# LED_Matrix.net
KiCad netlist of a schematic drawn in Altium Designer
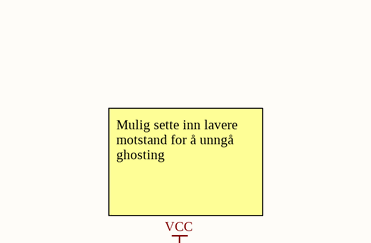
[diagram p0: LED Matrix.SchDoc, top left]
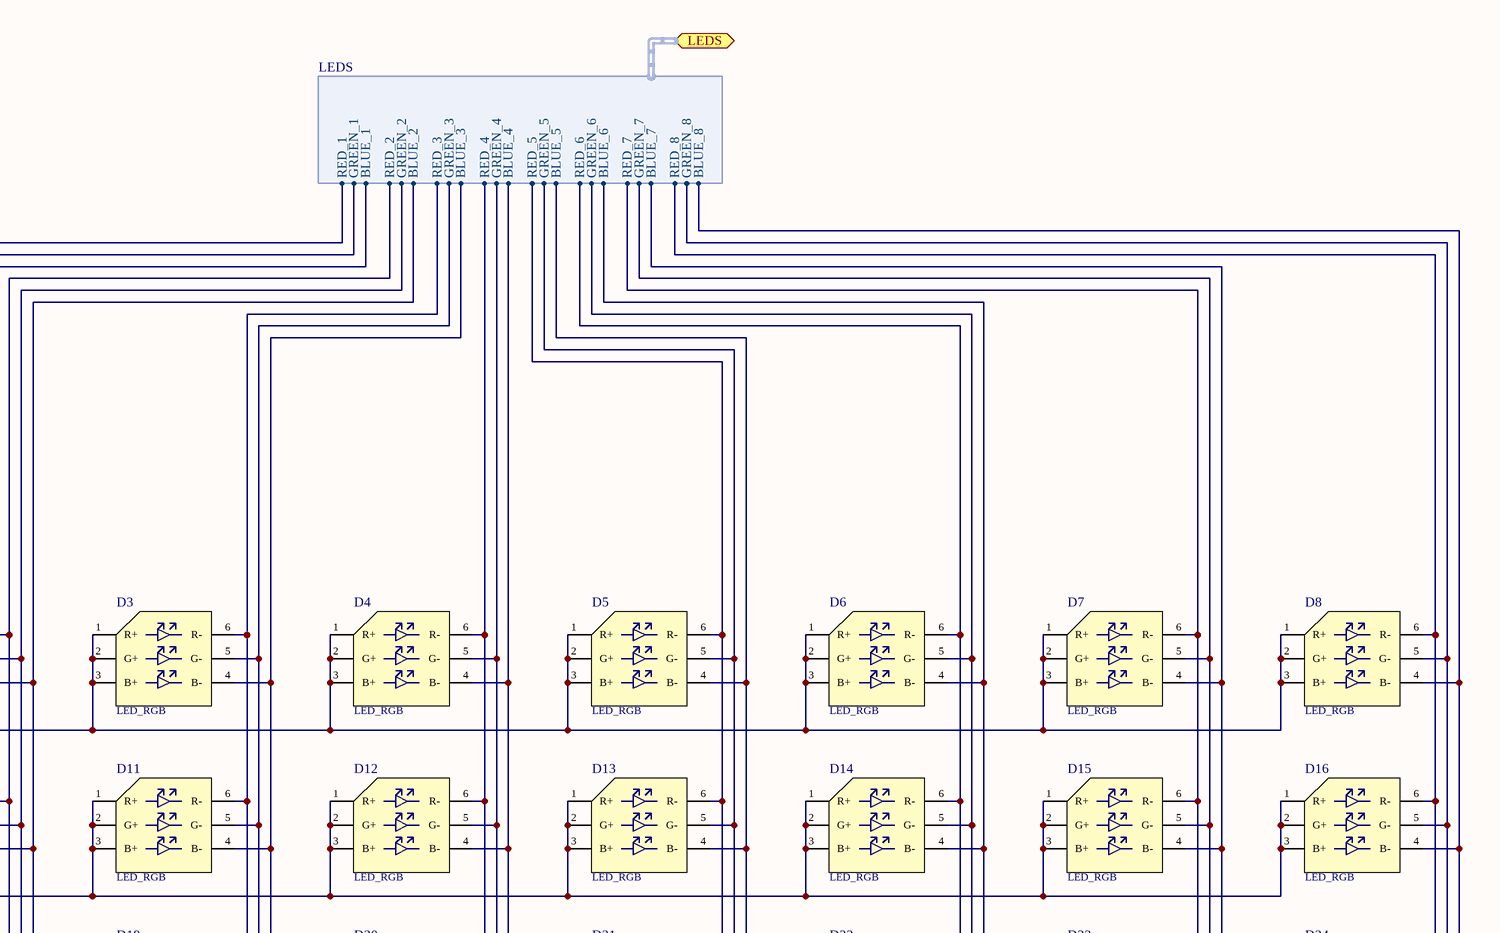
[diagram p1: LED Matrix.SchDoc, top right]
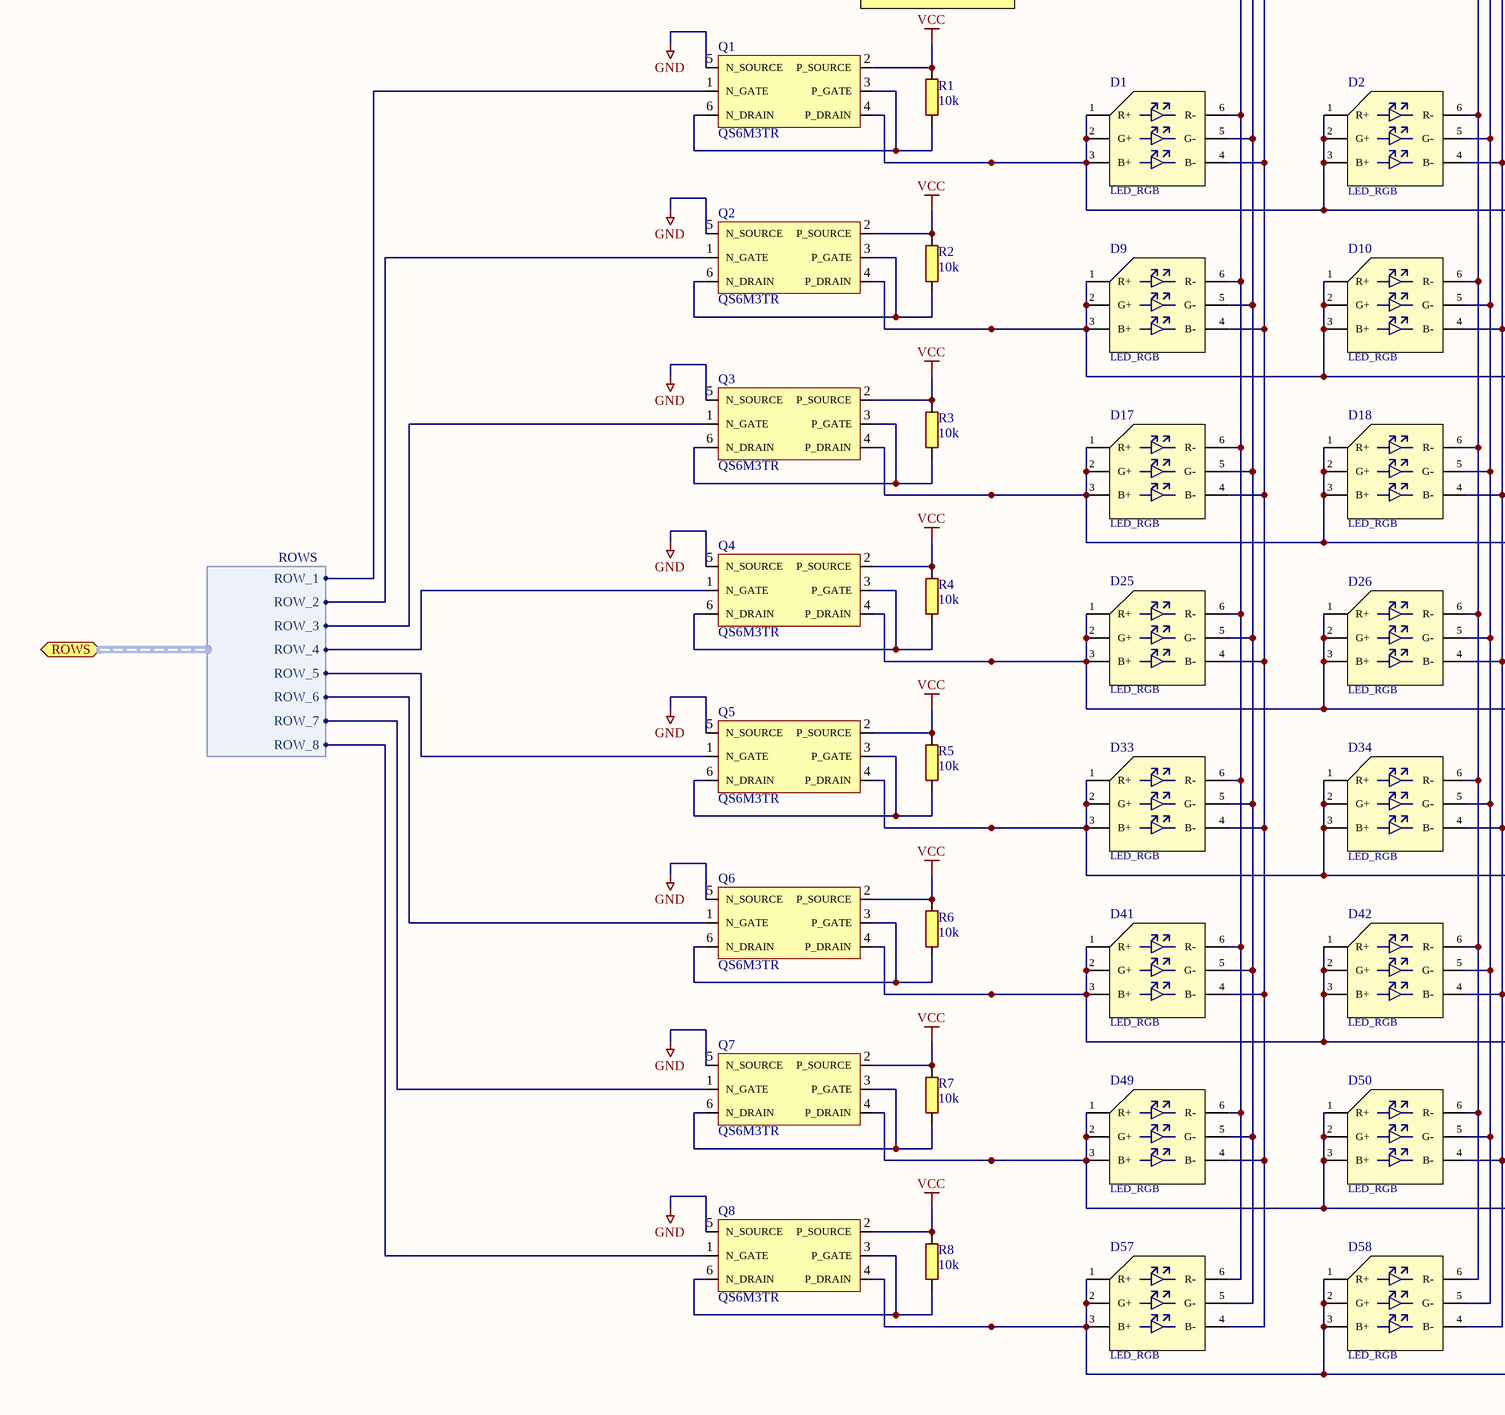
[diagram p2: LED Matrix.SchDoc, bottom left]
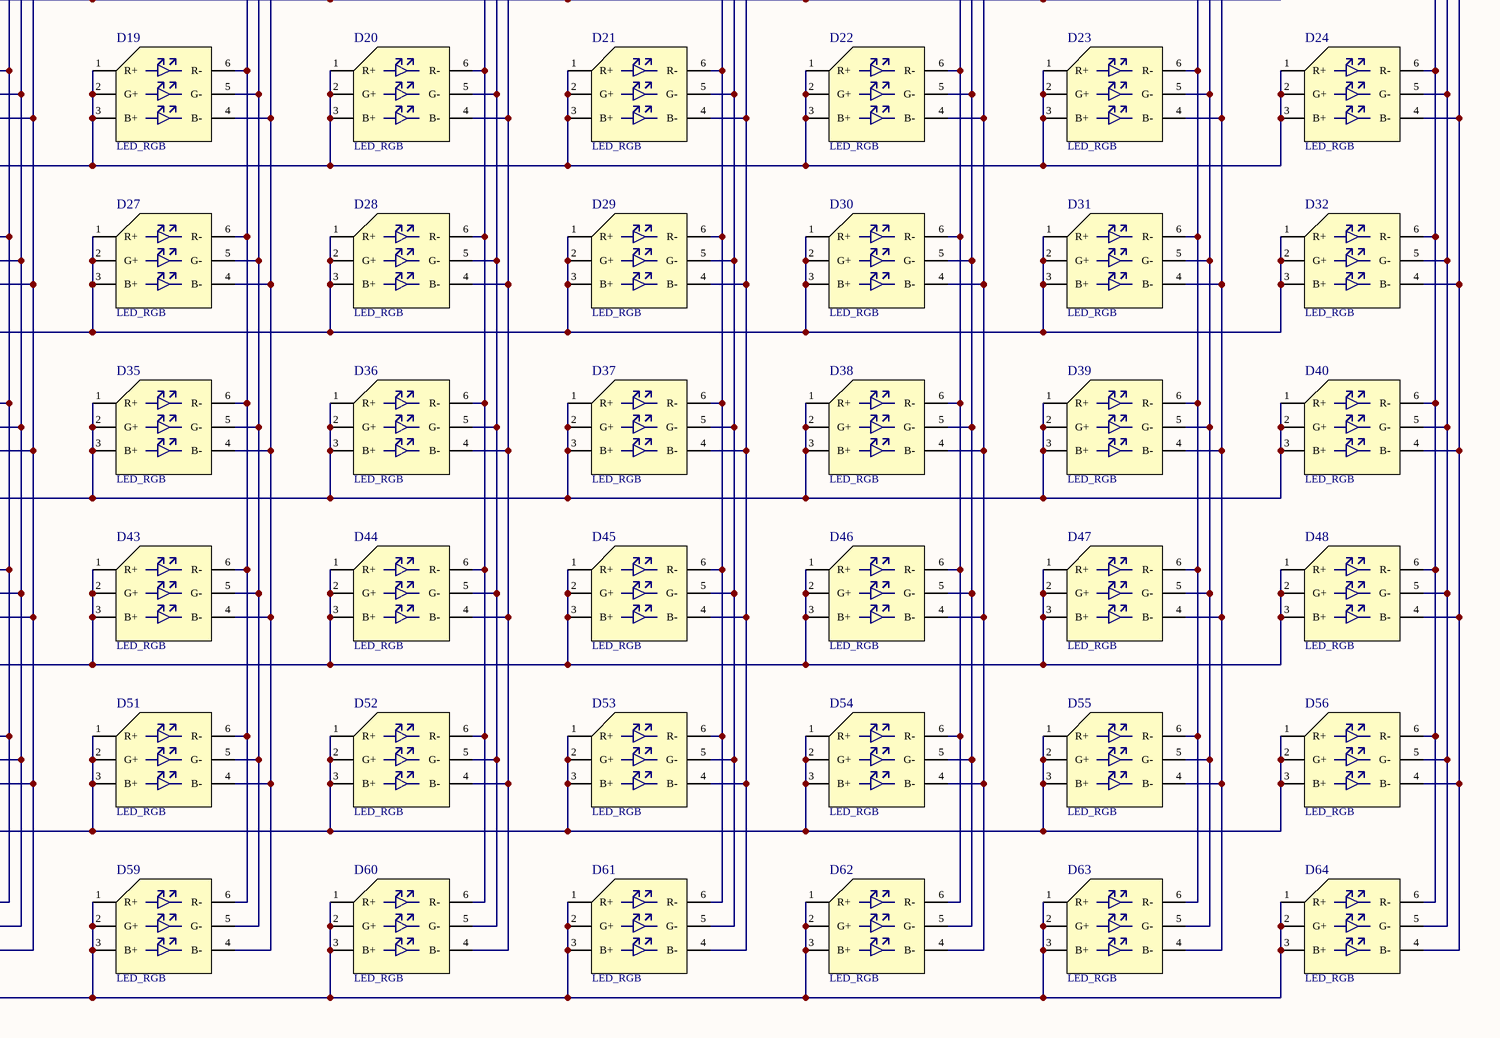
[diagram p3: LED Matrix.SchDoc, bottom right]

(export (version "E")
  (design (tool "Eeschema 10.0.6"))
  (components
    (comp (ref "D1")
      (value "LED_RGB")
      (footprint "LED5050_RGB_N")
      (description "LED RGB, independent colors")
      (libsource (lib "OVLib") (part "LED_RGB_IND_CHIP"))
    )
    (comp (ref "D2")
      (value "LED_RGB")
      (footprint "LED5050_RGB_N")
      (description "LED RGB, independent colors")
      (libsource (lib "OVLib") (part "LED_RGB_IND_CHIP"))
    )
    (comp (ref "D3")
      (value "LED_RGB")
      (footprint "LED5050_RGB_N")
      (description "LED RGB, independent colors")
      (libsource (lib "OVLib") (part "LED_RGB_IND_CHIP"))
    )
    (comp (ref "D4")
      (value "LED_RGB")
      (footprint "LED5050_RGB_N")
      (description "LED RGB, independent colors")
      (libsource (lib "OVLib") (part "LED_RGB_IND_CHIP"))
    )
    (comp (ref "D5")
      (value "LED_RGB")
      (footprint "LED5050_RGB_N")
      (description "LED RGB, independent colors")
      (libsource (lib "OVLib") (part "LED_RGB_IND_CHIP"))
    )
    (comp (ref "D6")
      (value "LED_RGB")
      (footprint "LED5050_RGB_N")
      (description "LED RGB, independent colors")
      (libsource (lib "OVLib") (part "LED_RGB_IND_CHIP"))
    )
    (comp (ref "D7")
      (value "LED_RGB")
      (footprint "LED5050_RGB_N")
      (description "LED RGB, independent colors")
      (libsource (lib "OVLib") (part "LED_RGB_IND_CHIP"))
    )
    (comp (ref "D8")
      (value "LED_RGB")
      (footprint "LED5050_RGB_N")
      (description "LED RGB, independent colors")
      (libsource (lib "OVLib") (part "LED_RGB_IND_CHIP"))
    )
    (comp (ref "D9")
      (value "LED_RGB")
      (footprint "LED5050_RGB_N")
      (description "LED RGB, independent colors")
      (libsource (lib "OVLib") (part "LED_RGB_IND_CHIP"))
    )
    (comp (ref "D10")
      (value "LED_RGB")
      (footprint "LED5050_RGB_N")
      (description "LED RGB, independent colors")
      (libsource (lib "OVLib") (part "LED_RGB_IND_CHIP"))
    )
    (comp (ref "D11")
      (value "LED_RGB")
      (footprint "LED5050_RGB_N")
      (description "LED RGB, independent colors")
      (libsource (lib "OVLib") (part "LED_RGB_IND_CHIP"))
    )
    (comp (ref "D12")
      (value "LED_RGB")
      (footprint "LED5050_RGB_N")
      (description "LED RGB, independent colors")
      (libsource (lib "OVLib") (part "LED_RGB_IND_CHIP"))
    )
    (comp (ref "D13")
      (value "LED_RGB")
      (footprint "LED5050_RGB_N")
      (description "LED RGB, independent colors")
      (libsource (lib "OVLib") (part "LED_RGB_IND_CHIP"))
    )
    (comp (ref "D14")
      (value "LED_RGB")
      (footprint "LED5050_RGB_N")
      (description "LED RGB, independent colors")
      (libsource (lib "OVLib") (part "LED_RGB_IND_CHIP"))
    )
    (comp (ref "D15")
      (value "LED_RGB")
      (footprint "LED5050_RGB_N")
      (description "LED RGB, independent colors")
      (libsource (lib "OVLib") (part "LED_RGB_IND_CHIP"))
    )
    (comp (ref "D16")
      (value "LED_RGB")
      (footprint "LED5050_RGB_N")
      (description "LED RGB, independent colors")
      (libsource (lib "OVLib") (part "LED_RGB_IND_CHIP"))
    )
    (comp (ref "D17")
      (value "LED_RGB")
      (footprint "LED5050_RGB_N")
      (description "LED RGB, independent colors")
      (libsource (lib "OVLib") (part "LED_RGB_IND_CHIP"))
    )
    (comp (ref "D18")
      (value "LED_RGB")
      (footprint "LED5050_RGB_N")
      (description "LED RGB, independent colors")
      (libsource (lib "OVLib") (part "LED_RGB_IND_CHIP"))
    )
    (comp (ref "D19")
      (value "LED_RGB")
      (footprint "LED5050_RGB_N")
      (description "LED RGB, independent colors")
      (libsource (lib "OVLib") (part "LED_RGB_IND_CHIP"))
    )
    (comp (ref "D20")
      (value "LED_RGB")
      (footprint "LED5050_RGB_N")
      (description "LED RGB, independent colors")
      (libsource (lib "OVLib") (part "LED_RGB_IND_CHIP"))
    )
    (comp (ref "D21")
      (value "LED_RGB")
      (footprint "LED5050_RGB_N")
      (description "LED RGB, independent colors")
      (libsource (lib "OVLib") (part "LED_RGB_IND_CHIP"))
    )
    (comp (ref "D22")
      (value "LED_RGB")
      (footprint "LED5050_RGB_N")
      (description "LED RGB, independent colors")
      (libsource (lib "OVLib") (part "LED_RGB_IND_CHIP"))
    )
    (comp (ref "D23")
      (value "LED_RGB")
      (footprint "LED5050_RGB_N")
      (description "LED RGB, independent colors")
      (libsource (lib "OVLib") (part "LED_RGB_IND_CHIP"))
    )
    (comp (ref "D24")
      (value "LED_RGB")
      (footprint "LED5050_RGB_N")
      (description "LED RGB, independent colors")
      (libsource (lib "OVLib") (part "LED_RGB_IND_CHIP"))
    )
    (comp (ref "D25")
      (value "LED_RGB")
      (footprint "LED5050_RGB_N")
      (description "LED RGB, independent colors")
      (libsource (lib "OVLib") (part "LED_RGB_IND_CHIP"))
    )
    (comp (ref "D26")
      (value "LED_RGB")
      (footprint "LED5050_RGB_N")
      (description "LED RGB, independent colors")
      (libsource (lib "OVLib") (part "LED_RGB_IND_CHIP"))
    )
    (comp (ref "D27")
      (value "LED_RGB")
      (footprint "LED5050_RGB_N")
      (description "LED RGB, independent colors")
      (libsource (lib "OVLib") (part "LED_RGB_IND_CHIP"))
    )
    (comp (ref "D28")
      (value "LED_RGB")
      (footprint "LED5050_RGB_N")
      (description "LED RGB, independent colors")
      (libsource (lib "OVLib") (part "LED_RGB_IND_CHIP"))
    )
    (comp (ref "D29")
      (value "LED_RGB")
      (footprint "LED5050_RGB_N")
      (description "LED RGB, independent colors")
      (libsource (lib "OVLib") (part "LED_RGB_IND_CHIP"))
    )
    (comp (ref "D30")
      (value "LED_RGB")
      (footprint "LED5050_RGB_N")
      (description "LED RGB, independent colors")
      (libsource (lib "OVLib") (part "LED_RGB_IND_CHIP"))
    )
    (comp (ref "D31")
      (value "LED_RGB")
      (footprint "LED5050_RGB_N")
      (description "LED RGB, independent colors")
      (libsource (lib "OVLib") (part "LED_RGB_IND_CHIP"))
    )
    (comp (ref "D32")
      (value "LED_RGB")
      (footprint "LED5050_RGB_N")
      (description "LED RGB, independent colors")
      (libsource (lib "OVLib") (part "LED_RGB_IND_CHIP"))
    )
    (comp (ref "D33")
      (value "LED_RGB")
      (footprint "LED5050_RGB_N")
      (description "LED RGB, independent colors")
      (libsource (lib "OVLib") (part "LED_RGB_IND_CHIP"))
    )
    (comp (ref "D34")
      (value "LED_RGB")
      (footprint "LED5050_RGB_N")
      (description "LED RGB, independent colors")
      (libsource (lib "OVLib") (part "LED_RGB_IND_CHIP"))
    )
    (comp (ref "D35")
      (value "LED_RGB")
      (footprint "LED5050_RGB_N")
      (description "LED RGB, independent colors")
      (libsource (lib "OVLib") (part "LED_RGB_IND_CHIP"))
    )
    (comp (ref "D36")
      (value "LED_RGB")
      (footprint "LED5050_RGB_N")
      (description "LED RGB, independent colors")
      (libsource (lib "OVLib") (part "LED_RGB_IND_CHIP"))
    )
    (comp (ref "D37")
      (value "LED_RGB")
      (footprint "LED5050_RGB_N")
      (description "LED RGB, independent colors")
      (libsource (lib "OVLib") (part "LED_RGB_IND_CHIP"))
    )
    (comp (ref "D38")
      (value "LED_RGB")
      (footprint "LED5050_RGB_N")
      (description "LED RGB, independent colors")
      (libsource (lib "OVLib") (part "LED_RGB_IND_CHIP"))
    )
    (comp (ref "D39")
      (value "LED_RGB")
      (footprint "LED5050_RGB_N")
      (description "LED RGB, independent colors")
      (libsource (lib "OVLib") (part "LED_RGB_IND_CHIP"))
    )
    (comp (ref "D40")
      (value "LED_RGB")
      (footprint "LED5050_RGB_N")
      (description "LED RGB, independent colors")
      (libsource (lib "OVLib") (part "LED_RGB_IND_CHIP"))
    )
    (comp (ref "D41")
      (value "LED_RGB")
      (footprint "LED5050_RGB_N")
      (description "LED RGB, independent colors")
      (libsource (lib "OVLib") (part "LED_RGB_IND_CHIP"))
    )
    (comp (ref "D42")
      (value "LED_RGB")
      (footprint "LED5050_RGB_N")
      (description "LED RGB, independent colors")
      (libsource (lib "OVLib") (part "LED_RGB_IND_CHIP"))
    )
    (comp (ref "D43")
      (value "LED_RGB")
      (footprint "LED5050_RGB_N")
      (description "LED RGB, independent colors")
      (libsource (lib "OVLib") (part "LED_RGB_IND_CHIP"))
    )
    (comp (ref "D44")
      (value "LED_RGB")
      (footprint "LED5050_RGB_N")
      (description "LED RGB, independent colors")
      (libsource (lib "OVLib") (part "LED_RGB_IND_CHIP"))
    )
    (comp (ref "D45")
      (value "LED_RGB")
      (footprint "LED5050_RGB_N")
      (description "LED RGB, independent colors")
      (libsource (lib "OVLib") (part "LED_RGB_IND_CHIP"))
    )
    (comp (ref "D46")
      (value "LED_RGB")
      (footprint "LED5050_RGB_N")
      (description "LED RGB, independent colors")
      (libsource (lib "OVLib") (part "LED_RGB_IND_CHIP"))
    )
    (comp (ref "D47")
      (value "LED_RGB")
      (footprint "LED5050_RGB_N")
      (description "LED RGB, independent colors")
      (libsource (lib "OVLib") (part "LED_RGB_IND_CHIP"))
    )
    (comp (ref "D48")
      (value "LED_RGB")
      (footprint "LED5050_RGB_N")
      (description "LED RGB, independent colors")
      (libsource (lib "OVLib") (part "LED_RGB_IND_CHIP"))
    )
    (comp (ref "D49")
      (value "LED_RGB")
      (footprint "LED5050_RGB_N")
      (description "LED RGB, independent colors")
      (libsource (lib "OVLib") (part "LED_RGB_IND_CHIP"))
    )
    (comp (ref "D50")
      (value "LED_RGB")
      (footprint "LED5050_RGB_N")
      (description "LED RGB, independent colors")
      (libsource (lib "OVLib") (part "LED_RGB_IND_CHIP"))
    )
    (comp (ref "D51")
      (value "LED_RGB")
      (footprint "LED5050_RGB_N")
      (description "LED RGB, independent colors")
      (libsource (lib "OVLib") (part "LED_RGB_IND_CHIP"))
    )
    (comp (ref "D52")
      (value "LED_RGB")
      (footprint "LED5050_RGB_N")
      (description "LED RGB, independent colors")
      (libsource (lib "OVLib") (part "LED_RGB_IND_CHIP"))
    )
    (comp (ref "D53")
      (value "LED_RGB")
      (footprint "LED5050_RGB_N")
      (description "LED RGB, independent colors")
      (libsource (lib "OVLib") (part "LED_RGB_IND_CHIP"))
    )
    (comp (ref "D54")
      (value "LED_RGB")
      (footprint "LED5050_RGB_N")
      (description "LED RGB, independent colors")
      (libsource (lib "OVLib") (part "LED_RGB_IND_CHIP"))
    )
    (comp (ref "D55")
      (value "LED_RGB")
      (footprint "LED5050_RGB_N")
      (description "LED RGB, independent colors")
      (libsource (lib "OVLib") (part "LED_RGB_IND_CHIP"))
    )
    (comp (ref "D56")
      (value "LED_RGB")
      (footprint "LED5050_RGB_N")
      (description "LED RGB, independent colors")
      (libsource (lib "OVLib") (part "LED_RGB_IND_CHIP"))
    )
    (comp (ref "D57")
      (value "LED_RGB")
      (footprint "LED5050_RGB_N")
      (description "LED RGB, independent colors")
      (libsource (lib "OVLib") (part "LED_RGB_IND_CHIP"))
    )
    (comp (ref "D58")
      (value "LED_RGB")
      (footprint "LED5050_RGB_N")
      (description "LED RGB, independent colors")
      (libsource (lib "OVLib") (part "LED_RGB_IND_CHIP"))
    )
    (comp (ref "D59")
      (value "LED_RGB")
      (footprint "LED5050_RGB_N")
      (description "LED RGB, independent colors")
      (libsource (lib "OVLib") (part "LED_RGB_IND_CHIP"))
    )
    (comp (ref "D60")
      (value "LED_RGB")
      (footprint "LED5050_RGB_N")
      (description "LED RGB, independent colors")
      (libsource (lib "OVLib") (part "LED_RGB_IND_CHIP"))
    )
    (comp (ref "D61")
      (value "LED_RGB")
      (footprint "LED5050_RGB_N")
      (description "LED RGB, independent colors")
      (libsource (lib "OVLib") (part "LED_RGB_IND_CHIP"))
    )
    (comp (ref "D62")
      (value "LED_RGB")
      (footprint "LED5050_RGB_N")
      (description "LED RGB, independent colors")
      (libsource (lib "OVLib") (part "LED_RGB_IND_CHIP"))
    )
    (comp (ref "D63")
      (value "LED_RGB")
      (footprint "LED5050_RGB_N")
      (description "LED RGB, independent colors")
      (libsource (lib "OVLib") (part "LED_RGB_IND_CHIP"))
    )
    (comp (ref "D64")
      (value "LED_RGB")
      (footprint "LED5050_RGB_N")
      (description "LED RGB, independent colors")
      (libsource (lib "OVLib") (part "LED_RGB_IND_CHIP"))
    )
    (comp (ref "Q1") (value "QS6M3TR") (footprint "QS6M3TR") (libsource (lib "Schlib1") (part "QS6M3TR")))
    (comp (ref "Q2") (value "QS6M3TR") (footprint "QS6M3TR") (libsource (lib "Schlib1") (part "QS6M3TR")))
    (comp (ref "Q3") (value "QS6M3TR") (footprint "QS6M3TR") (libsource (lib "Schlib1") (part "QS6M3TR")))
    (comp (ref "Q4") (value "QS6M3TR") (footprint "QS6M3TR") (libsource (lib "Schlib1") (part "QS6M3TR")))
    (comp (ref "Q5") (value "QS6M3TR") (footprint "QS6M3TR") (libsource (lib "Schlib1") (part "QS6M3TR")))
    (comp (ref "Q6") (value "QS6M3TR") (footprint "QS6M3TR") (libsource (lib "Schlib1") (part "QS6M3TR")))
    (comp (ref "Q7") (value "QS6M3TR") (footprint "QS6M3TR") (libsource (lib "Schlib1") (part "QS6M3TR")))
    (comp (ref "Q8") (value "QS6M3TR") (footprint "QS6M3TR") (libsource (lib "Schlib1") (part "QS6M3TR")))
    (comp (ref "R1")
      (value "10k")
      (footprint "RESC0603(1608)_N")
      (description "0.1W 1% Thick film resistor")
      (libsource (lib "OVLib") (part "Resistor2"))
    )
    (comp (ref "R2")
      (value "10k")
      (footprint "RESC0603(1608)_N")
      (description "0.1W 1% Thick film resistor")
      (libsource (lib "OVLib") (part "Resistor2"))
    )
    (comp (ref "R3")
      (value "10k")
      (footprint "RESC0603(1608)_N")
      (description "0.1W 1% Thick film resistor")
      (libsource (lib "OVLib") (part "Resistor2"))
    )
    (comp (ref "R4")
      (value "10k")
      (footprint "RESC0603(1608)_N")
      (description "0.1W 1% Thick film resistor")
      (libsource (lib "OVLib") (part "Resistor2"))
    )
    (comp (ref "R5")
      (value "10k")
      (footprint "RESC0603(1608)_N")
      (description "0.1W 1% Thick film resistor")
      (libsource (lib "OVLib") (part "Resistor2"))
    )
    (comp (ref "R6")
      (value "10k")
      (footprint "RESC0603(1608)_N")
      (description "0.1W 1% Thick film resistor")
      (libsource (lib "OVLib") (part "Resistor2"))
    )
    (comp (ref "R7")
      (value "10k")
      (footprint "RESC0603(1608)_N")
      (description "0.1W 1% Thick film resistor")
      (libsource (lib "OVLib") (part "Resistor2"))
    )
    (comp (ref "R8")
      (value "10k")
      (footprint "RESC0603(1608)_N")
      (description "0.1W 1% Thick film resistor")
      (libsource (lib "OVLib") (part "Resistor2"))
    )
  )
  (nets
    (net (code "3") (name "/BLUE_4") (class "Default")
      (node (ref "D12") (pin "4") (pinfunction "B-_4") (pintype "power_in"))
      (node (ref "D20") (pin "4") (pinfunction "B-_4") (pintype "power_in"))
      (node (ref "D28") (pin "4") (pinfunction "B-_4") (pintype "power_in"))
      (node (ref "D36") (pin "4") (pinfunction "B-_4") (pintype "power_in"))
      (node (ref "D4") (pin "4") (pinfunction "B-_4") (pintype "power_in"))
      (node (ref "D44") (pin "4") (pinfunction "B-_4") (pintype "power_in"))
      (node (ref "D52") (pin "4") (pinfunction "B-_4") (pintype "power_in"))
      (node (ref "D60") (pin "4") (pinfunction "B-_4") (pintype "power_in"))
    )
    (net (code "4") (name "/GREEN_4") (class "Default")
      (node (ref "D12") (pin "5") (pinfunction "G-_5") (pintype "power_in"))
      (node (ref "D20") (pin "5") (pinfunction "G-_5") (pintype "power_in"))
      (node (ref "D28") (pin "5") (pinfunction "G-_5") (pintype "power_in"))
      (node (ref "D36") (pin "5") (pinfunction "G-_5") (pintype "power_in"))
      (node (ref "D4") (pin "5") (pinfunction "G-_5") (pintype "power_in"))
      (node (ref "D44") (pin "5") (pinfunction "G-_5") (pintype "power_in"))
      (node (ref "D52") (pin "5") (pinfunction "G-_5") (pintype "power_in"))
      (node (ref "D60") (pin "5") (pinfunction "G-_5") (pintype "power_in"))
    )
    (net (code "7") (name "GND") (class "Default")
      (node (ref "Q1") (pin "5") (pinfunction "N_SOURCE_5") (pintype "passive"))
      (node (ref "Q2") (pin "5") (pinfunction "N_SOURCE_5") (pintype "passive"))
      (node (ref "Q3") (pin "5") (pinfunction "N_SOURCE_5") (pintype "passive"))
      (node (ref "Q4") (pin "5") (pinfunction "N_SOURCE_5") (pintype "passive"))
      (node (ref "Q5") (pin "5") (pinfunction "N_SOURCE_5") (pintype "passive"))
      (node (ref "Q6") (pin "5") (pinfunction "N_SOURCE_5") (pintype "passive"))
      (node (ref "Q7") (pin "5") (pinfunction "N_SOURCE_5") (pintype "passive"))
      (node (ref "Q8") (pin "5") (pinfunction "N_SOURCE_5") (pintype "passive"))
    )
    (net (code "8") (name "Net-(D1-B+)") (class "Default")
      (node (ref "D1") (pin "1") (pinfunction "R+_1") (pintype "power_in"))
      (node (ref "D1") (pin "2") (pinfunction "G+_2") (pintype "power_in"))
      (node (ref "D1") (pin "3") (pinfunction "B+_3") (pintype "power_in"))
      (node (ref "D2") (pin "1") (pinfunction "R+_1") (pintype "power_in"))
      (node (ref "D2") (pin "2") (pinfunction "G+_2") (pintype "power_in"))
      (node (ref "D2") (pin "3") (pinfunction "B+_3") (pintype "power_in"))
      (node (ref "D3") (pin "1") (pinfunction "R+_1") (pintype "power_in"))
      (node (ref "D3") (pin "2") (pinfunction "G+_2") (pintype "power_in"))
      (node (ref "D3") (pin "3") (pinfunction "B+_3") (pintype "power_in"))
      (node (ref "D4") (pin "1") (pinfunction "R+_1") (pintype "power_in"))
      (node (ref "D4") (pin "2") (pinfunction "G+_2") (pintype "power_in"))
      (node (ref "D4") (pin "3") (pinfunction "B+_3") (pintype "power_in"))
      (node (ref "D5") (pin "1") (pinfunction "R+_1") (pintype "power_in"))
      (node (ref "D5") (pin "2") (pinfunction "G+_2") (pintype "power_in"))
      (node (ref "D5") (pin "3") (pinfunction "B+_3") (pintype "power_in"))
      (node (ref "D6") (pin "1") (pinfunction "R+_1") (pintype "power_in"))
      (node (ref "D6") (pin "2") (pinfunction "G+_2") (pintype "power_in"))
      (node (ref "D6") (pin "3") (pinfunction "B+_3") (pintype "power_in"))
      (node (ref "D7") (pin "1") (pinfunction "R+_1") (pintype "power_in"))
      (node (ref "D7") (pin "2") (pinfunction "G+_2") (pintype "power_in"))
      (node (ref "D7") (pin "3") (pinfunction "B+_3") (pintype "power_in"))
      (node (ref "D8") (pin "1") (pinfunction "R+_1") (pintype "power_in"))
      (node (ref "D8") (pin "2") (pinfunction "G+_2") (pintype "power_in"))
      (node (ref "D8") (pin "3") (pinfunction "B+_3") (pintype "power_in"))
      (node (ref "Q1") (pin "4") (pinfunction "P_DRAIN_4") (pintype "passive"))
    )
    (net (code "9") (name "Net-(D1-B-)") (class "Default")
      (node (ref "D1") (pin "4") (pinfunction "B-_4") (pintype "power_in"))
      (node (ref "D17") (pin "4") (pinfunction "B-_4") (pintype "power_in"))
      (node (ref "D25") (pin "4") (pinfunction "B-_4") (pintype "power_in"))
      (node (ref "D33") (pin "4") (pinfunction "B-_4") (pintype "power_in"))
      (node (ref "D41") (pin "4") (pinfunction "B-_4") (pintype "power_in"))
      (node (ref "D49") (pin "4") (pinfunction "B-_4") (pintype "power_in"))
      (node (ref "D57") (pin "4") (pinfunction "B-_4") (pintype "power_in"))
      (node (ref "D9") (pin "4") (pinfunction "B-_4") (pintype "power_in"))
    )
    (net (code "10") (name "Net-(D1-G-)") (class "Default")
      (node (ref "D1") (pin "5") (pinfunction "G-_5") (pintype "power_in"))
      (node (ref "D17") (pin "5") (pinfunction "G-_5") (pintype "power_in"))
      (node (ref "D25") (pin "5") (pinfunction "G-_5") (pintype "power_in"))
      (node (ref "D33") (pin "5") (pinfunction "G-_5") (pintype "power_in"))
      (node (ref "D41") (pin "5") (pinfunction "G-_5") (pintype "power_in"))
      (node (ref "D49") (pin "5") (pinfunction "G-_5") (pintype "power_in"))
      (node (ref "D57") (pin "5") (pinfunction "G-_5") (pintype "power_in"))
      (node (ref "D9") (pin "5") (pinfunction "G-_5") (pintype "power_in"))
    )
    (net (code "11") (name "Net-(D1-R-)") (class "Default")
      (node (ref "D1") (pin "6") (pinfunction "R-_6") (pintype "power_in"))
      (node (ref "D17") (pin "6") (pinfunction "R-_6") (pintype "power_in"))
      (node (ref "D25") (pin "6") (pinfunction "R-_6") (pintype "power_in"))
      (node (ref "D33") (pin "6") (pinfunction "R-_6") (pintype "power_in"))
      (node (ref "D41") (pin "6") (pinfunction "R-_6") (pintype "power_in"))
      (node (ref "D49") (pin "6") (pinfunction "R-_6") (pintype "power_in"))
      (node (ref "D57") (pin "6") (pinfunction "R-_6") (pintype "power_in"))
      (node (ref "D9") (pin "6") (pinfunction "R-_6") (pintype "power_in"))
    )
    (net (code "12") (name "Net-(D10-B+)") (class "Default")
      (node (ref "D10") (pin "1") (pinfunction "R+_1") (pintype "power_in"))
      (node (ref "D10") (pin "2") (pinfunction "G+_2") (pintype "power_in"))
      (node (ref "D10") (pin "3") (pinfunction "B+_3") (pintype "power_in"))
      (node (ref "D11") (pin "1") (pinfunction "R+_1") (pintype "power_in"))
      (node (ref "D11") (pin "2") (pinfunction "G+_2") (pintype "power_in"))
      (node (ref "D11") (pin "3") (pinfunction "B+_3") (pintype "power_in"))
      (node (ref "D12") (pin "1") (pinfunction "R+_1") (pintype "power_in"))
      (node (ref "D12") (pin "2") (pinfunction "G+_2") (pintype "power_in"))
      (node (ref "D12") (pin "3") (pinfunction "B+_3") (pintype "power_in"))
      (node (ref "D13") (pin "1") (pinfunction "R+_1") (pintype "power_in"))
      (node (ref "D13") (pin "2") (pinfunction "G+_2") (pintype "power_in"))
      (node (ref "D13") (pin "3") (pinfunction "B+_3") (pintype "power_in"))
      (node (ref "D14") (pin "1") (pinfunction "R+_1") (pintype "power_in"))
      (node (ref "D14") (pin "2") (pinfunction "G+_2") (pintype "power_in"))
      (node (ref "D14") (pin "3") (pinfunction "B+_3") (pintype "power_in"))
      (node (ref "D15") (pin "1") (pinfunction "R+_1") (pintype "power_in"))
      (node (ref "D15") (pin "2") (pinfunction "G+_2") (pintype "power_in"))
      (node (ref "D15") (pin "3") (pinfunction "B+_3") (pintype "power_in"))
      (node (ref "D16") (pin "1") (pinfunction "R+_1") (pintype "power_in"))
      (node (ref "D16") (pin "2") (pinfunction "G+_2") (pintype "power_in"))
      (node (ref "D16") (pin "3") (pinfunction "B+_3") (pintype "power_in"))
      (node (ref "D9") (pin "1") (pinfunction "R+_1") (pintype "power_in"))
      (node (ref "D9") (pin "2") (pinfunction "G+_2") (pintype "power_in"))
      (node (ref "D9") (pin "3") (pinfunction "B+_3") (pintype "power_in"))
      (node (ref "Q2") (pin "4") (pinfunction "P_DRAIN_4") (pintype "passive"))
    )
    (net (code "13") (name "Net-(D10-B-)") (class "Default")
      (node (ref "D10") (pin "4") (pinfunction "B-_4") (pintype "power_in"))
      (node (ref "D18") (pin "4") (pinfunction "B-_4") (pintype "power_in"))
      (node (ref "D2") (pin "4") (pinfunction "B-_4") (pintype "power_in"))
      (node (ref "D26") (pin "4") (pinfunction "B-_4") (pintype "power_in"))
      (node (ref "D34") (pin "4") (pinfunction "B-_4") (pintype "power_in"))
      (node (ref "D42") (pin "4") (pinfunction "B-_4") (pintype "power_in"))
      (node (ref "D50") (pin "4") (pinfunction "B-_4") (pintype "power_in"))
      (node (ref "D58") (pin "4") (pinfunction "B-_4") (pintype "power_in"))
    )
    (net (code "14") (name "Net-(D10-G-)") (class "Default")
      (node (ref "D10") (pin "5") (pinfunction "G-_5") (pintype "power_in"))
      (node (ref "D18") (pin "5") (pinfunction "G-_5") (pintype "power_in"))
      (node (ref "D2") (pin "5") (pinfunction "G-_5") (pintype "power_in"))
      (node (ref "D26") (pin "5") (pinfunction "G-_5") (pintype "power_in"))
      (node (ref "D34") (pin "5") (pinfunction "G-_5") (pintype "power_in"))
      (node (ref "D42") (pin "5") (pinfunction "G-_5") (pintype "power_in"))
      (node (ref "D50") (pin "5") (pinfunction "G-_5") (pintype "power_in"))
      (node (ref "D58") (pin "5") (pinfunction "G-_5") (pintype "power_in"))
    )
    (net (code "15") (name "Net-(D10-R-)") (class "Default")
      (node (ref "D10") (pin "6") (pinfunction "R-_6") (pintype "power_in"))
      (node (ref "D18") (pin "6") (pinfunction "R-_6") (pintype "power_in"))
      (node (ref "D2") (pin "6") (pinfunction "R-_6") (pintype "power_in"))
      (node (ref "D26") (pin "6") (pinfunction "R-_6") (pintype "power_in"))
      (node (ref "D34") (pin "6") (pinfunction "R-_6") (pintype "power_in"))
      (node (ref "D42") (pin "6") (pinfunction "R-_6") (pintype "power_in"))
      (node (ref "D50") (pin "6") (pinfunction "R-_6") (pintype "power_in"))
      (node (ref "D58") (pin "6") (pinfunction "R-_6") (pintype "power_in"))
    )
    (net (code "16") (name "Net-(D11-B-)") (class "Default")
      (node (ref "D11") (pin "4") (pinfunction "B-_4") (pintype "power_in"))
      (node (ref "D19") (pin "4") (pinfunction "B-_4") (pintype "power_in"))
      (node (ref "D27") (pin "4") (pinfunction "B-_4") (pintype "power_in"))
      (node (ref "D3") (pin "4") (pinfunction "B-_4") (pintype "power_in"))
      (node (ref "D35") (pin "4") (pinfunction "B-_4") (pintype "power_in"))
      (node (ref "D43") (pin "4") (pinfunction "B-_4") (pintype "power_in"))
      (node (ref "D51") (pin "4") (pinfunction "B-_4") (pintype "power_in"))
      (node (ref "D59") (pin "4") (pinfunction "B-_4") (pintype "power_in"))
    )
    (net (code "17") (name "Net-(D11-G-)") (class "Default")
      (node (ref "D11") (pin "5") (pinfunction "G-_5") (pintype "power_in"))
      (node (ref "D19") (pin "5") (pinfunction "G-_5") (pintype "power_in"))
      (node (ref "D27") (pin "5") (pinfunction "G-_5") (pintype "power_in"))
      (node (ref "D3") (pin "5") (pinfunction "G-_5") (pintype "power_in"))
      (node (ref "D35") (pin "5") (pinfunction "G-_5") (pintype "power_in"))
      (node (ref "D43") (pin "5") (pinfunction "G-_5") (pintype "power_in"))
      (node (ref "D51") (pin "5") (pinfunction "G-_5") (pintype "power_in"))
      (node (ref "D59") (pin "5") (pinfunction "G-_5") (pintype "power_in"))
    )
    (net (code "18") (name "Net-(D11-R-)") (class "Default")
      (node (ref "D11") (pin "6") (pinfunction "R-_6") (pintype "power_in"))
      (node (ref "D19") (pin "6") (pinfunction "R-_6") (pintype "power_in"))
      (node (ref "D27") (pin "6") (pinfunction "R-_6") (pintype "power_in"))
      (node (ref "D3") (pin "6") (pinfunction "R-_6") (pintype "power_in"))
      (node (ref "D35") (pin "6") (pinfunction "R-_6") (pintype "power_in"))
      (node (ref "D43") (pin "6") (pinfunction "R-_6") (pintype "power_in"))
      (node (ref "D51") (pin "6") (pinfunction "R-_6") (pintype "power_in"))
      (node (ref "D59") (pin "6") (pinfunction "R-_6") (pintype "power_in"))
    )
    (net (code "19") (name "Net-(D12-R-)") (class "Default")
      (node (ref "D12") (pin "6") (pinfunction "R-_6") (pintype "power_in"))
      (node (ref "D20") (pin "6") (pinfunction "R-_6") (pintype "power_in"))
      (node (ref "D28") (pin "6") (pinfunction "R-_6") (pintype "power_in"))
      (node (ref "D36") (pin "6") (pinfunction "R-_6") (pintype "power_in"))
      (node (ref "D4") (pin "6") (pinfunction "R-_6") (pintype "power_in"))
      (node (ref "D44") (pin "6") (pinfunction "R-_6") (pintype "power_in"))
      (node (ref "D52") (pin "6") (pinfunction "R-_6") (pintype "power_in"))
      (node (ref "D60") (pin "6") (pinfunction "R-_6") (pintype "power_in"))
    )
    (net (code "20") (name "Net-(D13-B-)") (class "Default")
      (node (ref "D13") (pin "4") (pinfunction "B-_4") (pintype "power_in"))
      (node (ref "D21") (pin "4") (pinfunction "B-_4") (pintype "power_in"))
      (node (ref "D29") (pin "4") (pinfunction "B-_4") (pintype "power_in"))
      (node (ref "D37") (pin "4") (pinfunction "B-_4") (pintype "power_in"))
      (node (ref "D45") (pin "4") (pinfunction "B-_4") (pintype "power_in"))
      (node (ref "D5") (pin "4") (pinfunction "B-_4") (pintype "power_in"))
      (node (ref "D53") (pin "4") (pinfunction "B-_4") (pintype "power_in"))
      (node (ref "D61") (pin "4") (pinfunction "B-_4") (pintype "power_in"))
    )
    (net (code "21") (name "Net-(D13-G-)") (class "Default")
      (node (ref "D13") (pin "5") (pinfunction "G-_5") (pintype "power_in"))
      (node (ref "D21") (pin "5") (pinfunction "G-_5") (pintype "power_in"))
      (node (ref "D29") (pin "5") (pinfunction "G-_5") (pintype "power_in"))
      (node (ref "D37") (pin "5") (pinfunction "G-_5") (pintype "power_in"))
      (node (ref "D45") (pin "5") (pinfunction "G-_5") (pintype "power_in"))
      (node (ref "D5") (pin "5") (pinfunction "G-_5") (pintype "power_in"))
      (node (ref "D53") (pin "5") (pinfunction "G-_5") (pintype "power_in"))
      (node (ref "D61") (pin "5") (pinfunction "G-_5") (pintype "power_in"))
    )
    (net (code "22") (name "Net-(D13-R-)") (class "Default")
      (node (ref "D13") (pin "6") (pinfunction "R-_6") (pintype "power_in"))
      (node (ref "D21") (pin "6") (pinfunction "R-_6") (pintype "power_in"))
      (node (ref "D29") (pin "6") (pinfunction "R-_6") (pintype "power_in"))
      (node (ref "D37") (pin "6") (pinfunction "R-_6") (pintype "power_in"))
      (node (ref "D45") (pin "6") (pinfunction "R-_6") (pintype "power_in"))
      (node (ref "D5") (pin "6") (pinfunction "R-_6") (pintype "power_in"))
      (node (ref "D53") (pin "6") (pinfunction "R-_6") (pintype "power_in"))
      (node (ref "D61") (pin "6") (pinfunction "R-_6") (pintype "power_in"))
    )
    (net (code "23") (name "Net-(D14-B-)") (class "Default")
      (node (ref "D14") (pin "4") (pinfunction "B-_4") (pintype "power_in"))
      (node (ref "D22") (pin "4") (pinfunction "B-_4") (pintype "power_in"))
      (node (ref "D30") (pin "4") (pinfunction "B-_4") (pintype "power_in"))
      (node (ref "D38") (pin "4") (pinfunction "B-_4") (pintype "power_in"))
      (node (ref "D46") (pin "4") (pinfunction "B-_4") (pintype "power_in"))
      (node (ref "D54") (pin "4") (pinfunction "B-_4") (pintype "power_in"))
      (node (ref "D6") (pin "4") (pinfunction "B-_4") (pintype "power_in"))
      (node (ref "D62") (pin "4") (pinfunction "B-_4") (pintype "power_in"))
    )
    (net (code "24") (name "Net-(D14-G-)") (class "Default")
      (node (ref "D14") (pin "5") (pinfunction "G-_5") (pintype "power_in"))
      (node (ref "D22") (pin "5") (pinfunction "G-_5") (pintype "power_in"))
      (node (ref "D30") (pin "5") (pinfunction "G-_5") (pintype "power_in"))
      (node (ref "D38") (pin "5") (pinfunction "G-_5") (pintype "power_in"))
      (node (ref "D46") (pin "5") (pinfunction "G-_5") (pintype "power_in"))
      (node (ref "D54") (pin "5") (pinfunction "G-_5") (pintype "power_in"))
      (node (ref "D6") (pin "5") (pinfunction "G-_5") (pintype "power_in"))
      (node (ref "D62") (pin "5") (pinfunction "G-_5") (pintype "power_in"))
    )
    (net (code "25") (name "Net-(D14-R-)") (class "Default")
      (node (ref "D14") (pin "6") (pinfunction "R-_6") (pintype "power_in"))
      (node (ref "D22") (pin "6") (pinfunction "R-_6") (pintype "power_in"))
      (node (ref "D30") (pin "6") (pinfunction "R-_6") (pintype "power_in"))
      (node (ref "D38") (pin "6") (pinfunction "R-_6") (pintype "power_in"))
      (node (ref "D46") (pin "6") (pinfunction "R-_6") (pintype "power_in"))
      (node (ref "D54") (pin "6") (pinfunction "R-_6") (pintype "power_in"))
      (node (ref "D6") (pin "6") (pinfunction "R-_6") (pintype "power_in"))
      (node (ref "D62") (pin "6") (pinfunction "R-_6") (pintype "power_in"))
    )
    (net (code "26") (name "Net-(D15-B-)") (class "Default")
      (node (ref "D15") (pin "4") (pinfunction "B-_4") (pintype "power_in"))
      (node (ref "D23") (pin "4") (pinfunction "B-_4") (pintype "power_in"))
      (node (ref "D31") (pin "4") (pinfunction "B-_4") (pintype "power_in"))
      (node (ref "D39") (pin "4") (pinfunction "B-_4") (pintype "power_in"))
      (node (ref "D47") (pin "4") (pinfunction "B-_4") (pintype "power_in"))
      (node (ref "D55") (pin "4") (pinfunction "B-_4") (pintype "power_in"))
      (node (ref "D63") (pin "4") (pinfunction "B-_4") (pintype "power_in"))
      (node (ref "D7") (pin "4") (pinfunction "B-_4") (pintype "power_in"))
    )
    (net (code "27") (name "Net-(D15-G-)") (class "Default")
      (node (ref "D15") (pin "5") (pinfunction "G-_5") (pintype "power_in"))
      (node (ref "D23") (pin "5") (pinfunction "G-_5") (pintype "power_in"))
      (node (ref "D31") (pin "5") (pinfunction "G-_5") (pintype "power_in"))
      (node (ref "D39") (pin "5") (pinfunction "G-_5") (pintype "power_in"))
      (node (ref "D47") (pin "5") (pinfunction "G-_5") (pintype "power_in"))
      (node (ref "D55") (pin "5") (pinfunction "G-_5") (pintype "power_in"))
      (node (ref "D63") (pin "5") (pinfunction "G-_5") (pintype "power_in"))
      (node (ref "D7") (pin "5") (pinfunction "G-_5") (pintype "power_in"))
    )
    (net (code "28") (name "Net-(D15-R-)") (class "Default")
      (node (ref "D15") (pin "6") (pinfunction "R-_6") (pintype "power_in"))
      (node (ref "D23") (pin "6") (pinfunction "R-_6") (pintype "power_in"))
      (node (ref "D31") (pin "6") (pinfunction "R-_6") (pintype "power_in"))
      (node (ref "D39") (pin "6") (pinfunction "R-_6") (pintype "power_in"))
      (node (ref "D47") (pin "6") (pinfunction "R-_6") (pintype "power_in"))
      (node (ref "D55") (pin "6") (pinfunction "R-_6") (pintype "power_in"))
      (node (ref "D63") (pin "6") (pinfunction "R-_6") (pintype "power_in"))
      (node (ref "D7") (pin "6") (pinfunction "R-_6") (pintype "power_in"))
    )
    (net (code "29") (name "Net-(D16-B-)") (class "Default")
      (node (ref "D16") (pin "4") (pinfunction "B-_4") (pintype "power_in"))
      (node (ref "D24") (pin "4") (pinfunction "B-_4") (pintype "power_in"))
      (node (ref "D32") (pin "4") (pinfunction "B-_4") (pintype "power_in"))
      (node (ref "D40") (pin "4") (pinfunction "B-_4") (pintype "power_in"))
      (node (ref "D48") (pin "4") (pinfunction "B-_4") (pintype "power_in"))
      (node (ref "D56") (pin "4") (pinfunction "B-_4") (pintype "power_in"))
      (node (ref "D64") (pin "4") (pinfunction "B-_4") (pintype "power_in"))
      (node (ref "D8") (pin "4") (pinfunction "B-_4") (pintype "power_in"))
    )
    (net (code "30") (name "Net-(D16-G-)") (class "Default")
      (node (ref "D16") (pin "5") (pinfunction "G-_5") (pintype "power_in"))
      (node (ref "D24") (pin "5") (pinfunction "G-_5") (pintype "power_in"))
      (node (ref "D32") (pin "5") (pinfunction "G-_5") (pintype "power_in"))
      (node (ref "D40") (pin "5") (pinfunction "G-_5") (pintype "power_in"))
      (node (ref "D48") (pin "5") (pinfunction "G-_5") (pintype "power_in"))
      (node (ref "D56") (pin "5") (pinfunction "G-_5") (pintype "power_in"))
      (node (ref "D64") (pin "5") (pinfunction "G-_5") (pintype "power_in"))
      (node (ref "D8") (pin "5") (pinfunction "G-_5") (pintype "power_in"))
    )
    (net (code "31") (name "Net-(D16-R-)") (class "Default")
      (node (ref "D16") (pin "6") (pinfunction "R-_6") (pintype "power_in"))
      (node (ref "D24") (pin "6") (pinfunction "R-_6") (pintype "power_in"))
      (node (ref "D32") (pin "6") (pinfunction "R-_6") (pintype "power_in"))
      (node (ref "D40") (pin "6") (pinfunction "R-_6") (pintype "power_in"))
      (node (ref "D48") (pin "6") (pinfunction "R-_6") (pintype "power_in"))
      (node (ref "D56") (pin "6") (pinfunction "R-_6") (pintype "power_in"))
      (node (ref "D64") (pin "6") (pinfunction "R-_6") (pintype "power_in"))
      (node (ref "D8") (pin "6") (pinfunction "R-_6") (pintype "power_in"))
    )
    (net (code "32") (name "Net-(D17-B+)") (class "Default")
      (node (ref "D17") (pin "1") (pinfunction "R+_1") (pintype "power_in"))
      (node (ref "D17") (pin "2") (pinfunction "G+_2") (pintype "power_in"))
      (node (ref "D17") (pin "3") (pinfunction "B+_3") (pintype "power_in"))
      (node (ref "D18") (pin "1") (pinfunction "R+_1") (pintype "power_in"))
      (node (ref "D18") (pin "2") (pinfunction "G+_2") (pintype "power_in"))
      (node (ref "D18") (pin "3") (pinfunction "B+_3") (pintype "power_in"))
      (node (ref "D19") (pin "1") (pinfunction "R+_1") (pintype "power_in"))
      (node (ref "D19") (pin "2") (pinfunction "G+_2") (pintype "power_in"))
      (node (ref "D19") (pin "3") (pinfunction "B+_3") (pintype "power_in"))
      (node (ref "D20") (pin "1") (pinfunction "R+_1") (pintype "power_in"))
      (node (ref "D20") (pin "2") (pinfunction "G+_2") (pintype "power_in"))
      (node (ref "D20") (pin "3") (pinfunction "B+_3") (pintype "power_in"))
      (node (ref "D21") (pin "1") (pinfunction "R+_1") (pintype "power_in"))
      (node (ref "D21") (pin "2") (pinfunction "G+_2") (pintype "power_in"))
      (node (ref "D21") (pin "3") (pinfunction "B+_3") (pintype "power_in"))
      (node (ref "D22") (pin "1") (pinfunction "R+_1") (pintype "power_in"))
      (node (ref "D22") (pin "2") (pinfunction "G+_2") (pintype "power_in"))
      (node (ref "D22") (pin "3") (pinfunction "B+_3") (pintype "power_in"))
      (node (ref "D23") (pin "1") (pinfunction "R+_1") (pintype "power_in"))
      (node (ref "D23") (pin "2") (pinfunction "G+_2") (pintype "power_in"))
      (node (ref "D23") (pin "3") (pinfunction "B+_3") (pintype "power_in"))
      (node (ref "D24") (pin "1") (pinfunction "R+_1") (pintype "power_in"))
      (node (ref "D24") (pin "2") (pinfunction "G+_2") (pintype "power_in"))
      (node (ref "D24") (pin "3") (pinfunction "B+_3") (pintype "power_in"))
      (node (ref "Q3") (pin "4") (pinfunction "P_DRAIN_4") (pintype "passive"))
    )
    (net (code "33") (name "Net-(D25-B+)") (class "Default")
      (node (ref "D25") (pin "1") (pinfunction "R+_1") (pintype "power_in"))
      (node (ref "D25") (pin "2") (pinfunction "G+_2") (pintype "power_in"))
      (node (ref "D25") (pin "3") (pinfunction "B+_3") (pintype "power_in"))
      (node (ref "D26") (pin "1") (pinfunction "R+_1") (pintype "power_in"))
      (node (ref "D26") (pin "2") (pinfunction "G+_2") (pintype "power_in"))
      (node (ref "D26") (pin "3") (pinfunction "B+_3") (pintype "power_in"))
      (node (ref "D27") (pin "1") (pinfunction "R+_1") (pintype "power_in"))
      (node (ref "D27") (pin "2") (pinfunction "G+_2") (pintype "power_in"))
      (node (ref "D27") (pin "3") (pinfunction "B+_3") (pintype "power_in"))
      (node (ref "D28") (pin "1") (pinfunction "R+_1") (pintype "power_in"))
      (node (ref "D28") (pin "2") (pinfunction "G+_2") (pintype "power_in"))
      (node (ref "D28") (pin "3") (pinfunction "B+_3") (pintype "power_in"))
      (node (ref "D29") (pin "1") (pinfunction "R+_1") (pintype "power_in"))
      (node (ref "D29") (pin "2") (pinfunction "G+_2") (pintype "power_in"))
      (node (ref "D29") (pin "3") (pinfunction "B+_3") (pintype "power_in"))
      (node (ref "D30") (pin "1") (pinfunction "R+_1") (pintype "power_in"))
      (node (ref "D30") (pin "2") (pinfunction "G+_2") (pintype "power_in"))
      (node (ref "D30") (pin "3") (pinfunction "B+_3") (pintype "power_in"))
      (node (ref "D31") (pin "1") (pinfunction "R+_1") (pintype "power_in"))
      (node (ref "D31") (pin "2") (pinfunction "G+_2") (pintype "power_in"))
      (node (ref "D31") (pin "3") (pinfunction "B+_3") (pintype "power_in"))
      (node (ref "D32") (pin "1") (pinfunction "R+_1") (pintype "power_in"))
      (node (ref "D32") (pin "2") (pinfunction "G+_2") (pintype "power_in"))
      (node (ref "D32") (pin "3") (pinfunction "B+_3") (pintype "power_in"))
      (node (ref "Q4") (pin "4") (pinfunction "P_DRAIN_4") (pintype "passive"))
    )
    (net (code "34") (name "Net-(D33-B+)") (class "Default")
      (node (ref "D33") (pin "1") (pinfunction "R+_1") (pintype "power_in"))
      (node (ref "D33") (pin "2") (pinfunction "G+_2") (pintype "power_in"))
      (node (ref "D33") (pin "3") (pinfunction "B+_3") (pintype "power_in"))
      (node (ref "D34") (pin "1") (pinfunction "R+_1") (pintype "power_in"))
      (node (ref "D34") (pin "2") (pinfunction "G+_2") (pintype "power_in"))
      (node (ref "D34") (pin "3") (pinfunction "B+_3") (pintype "power_in"))
      (node (ref "D35") (pin "1") (pinfunction "R+_1") (pintype "power_in"))
      (node (ref "D35") (pin "2") (pinfunction "G+_2") (pintype "power_in"))
      (node (ref "D35") (pin "3") (pinfunction "B+_3") (pintype "power_in"))
      (node (ref "D36") (pin "1") (pinfunction "R+_1") (pintype "power_in"))
      (node (ref "D36") (pin "2") (pinfunction "G+_2") (pintype "power_in"))
      (node (ref "D36") (pin "3") (pinfunction "B+_3") (pintype "power_in"))
      (node (ref "D37") (pin "1") (pinfunction "R+_1") (pintype "power_in"))
      (node (ref "D37") (pin "2") (pinfunction "G+_2") (pintype "power_in"))
      (node (ref "D37") (pin "3") (pinfunction "B+_3") (pintype "power_in"))
      (node (ref "D38") (pin "1") (pinfunction "R+_1") (pintype "power_in"))
      (node (ref "D38") (pin "2") (pinfunction "G+_2") (pintype "power_in"))
      (node (ref "D38") (pin "3") (pinfunction "B+_3") (pintype "power_in"))
      (node (ref "D39") (pin "1") (pinfunction "R+_1") (pintype "power_in"))
      (node (ref "D39") (pin "2") (pinfunction "G+_2") (pintype "power_in"))
      (node (ref "D39") (pin "3") (pinfunction "B+_3") (pintype "power_in"))
      (node (ref "D40") (pin "1") (pinfunction "R+_1") (pintype "power_in"))
      (node (ref "D40") (pin "2") (pinfunction "G+_2") (pintype "power_in"))
      (node (ref "D40") (pin "3") (pinfunction "B+_3") (pintype "power_in"))
      (node (ref "Q5") (pin "4") (pinfunction "P_DRAIN_4") (pintype "passive"))
    )
    (net (code "35") (name "Net-(D41-B+)") (class "Default")
      (node (ref "D41") (pin "1") (pinfunction "R+_1") (pintype "power_in"))
      (node (ref "D41") (pin "2") (pinfunction "G+_2") (pintype "power_in"))
      (node (ref "D41") (pin "3") (pinfunction "B+_3") (pintype "power_in"))
      (node (ref "D42") (pin "1") (pinfunction "R+_1") (pintype "power_in"))
      (node (ref "D42") (pin "2") (pinfunction "G+_2") (pintype "power_in"))
      (node (ref "D42") (pin "3") (pinfunction "B+_3") (pintype "power_in"))
      (node (ref "D43") (pin "1") (pinfunction "R+_1") (pintype "power_in"))
      (node (ref "D43") (pin "2") (pinfunction "G+_2") (pintype "power_in"))
      (node (ref "D43") (pin "3") (pinfunction "B+_3") (pintype "power_in"))
      (node (ref "D44") (pin "1") (pinfunction "R+_1") (pintype "power_in"))
      (node (ref "D44") (pin "2") (pinfunction "G+_2") (pintype "power_in"))
      (node (ref "D44") (pin "3") (pinfunction "B+_3") (pintype "power_in"))
      (node (ref "D45") (pin "1") (pinfunction "R+_1") (pintype "power_in"))
      (node (ref "D45") (pin "2") (pinfunction "G+_2") (pintype "power_in"))
      (node (ref "D45") (pin "3") (pinfunction "B+_3") (pintype "power_in"))
      (node (ref "D46") (pin "1") (pinfunction "R+_1") (pintype "power_in"))
      (node (ref "D46") (pin "2") (pinfunction "G+_2") (pintype "power_in"))
      (node (ref "D46") (pin "3") (pinfunction "B+_3") (pintype "power_in"))
      (node (ref "D47") (pin "1") (pinfunction "R+_1") (pintype "power_in"))
      (node (ref "D47") (pin "2") (pinfunction "G+_2") (pintype "power_in"))
      (node (ref "D47") (pin "3") (pinfunction "B+_3") (pintype "power_in"))
      (node (ref "D48") (pin "1") (pinfunction "R+_1") (pintype "power_in"))
      (node (ref "D48") (pin "2") (pinfunction "G+_2") (pintype "power_in"))
      (node (ref "D48") (pin "3") (pinfunction "B+_3") (pintype "power_in"))
      (node (ref "Q6") (pin "4") (pinfunction "P_DRAIN_4") (pintype "passive"))
    )
    (net (code "36") (name "Net-(D49-B+)") (class "Default")
      (node (ref "D49") (pin "1") (pinfunction "R+_1") (pintype "power_in"))
      (node (ref "D49") (pin "2") (pinfunction "G+_2") (pintype "power_in"))
      (node (ref "D49") (pin "3") (pinfunction "B+_3") (pintype "power_in"))
      (node (ref "D50") (pin "1") (pinfunction "R+_1") (pintype "power_in"))
      (node (ref "D50") (pin "2") (pinfunction "G+_2") (pintype "power_in"))
      (node (ref "D50") (pin "3") (pinfunction "B+_3") (pintype "power_in"))
      (node (ref "D51") (pin "1") (pinfunction "R+_1") (pintype "power_in"))
      (node (ref "D51") (pin "2") (pinfunction "G+_2") (pintype "power_in"))
      (node (ref "D51") (pin "3") (pinfunction "B+_3") (pintype "power_in"))
      (node (ref "D52") (pin "1") (pinfunction "R+_1") (pintype "power_in"))
      (node (ref "D52") (pin "2") (pinfunction "G+_2") (pintype "power_in"))
      (node (ref "D52") (pin "3") (pinfunction "B+_3") (pintype "power_in"))
      (node (ref "D53") (pin "1") (pinfunction "R+_1") (pintype "power_in"))
      (node (ref "D53") (pin "2") (pinfunction "G+_2") (pintype "power_in"))
      (node (ref "D53") (pin "3") (pinfunction "B+_3") (pintype "power_in"))
      (node (ref "D54") (pin "1") (pinfunction "R+_1") (pintype "power_in"))
      (node (ref "D54") (pin "2") (pinfunction "G+_2") (pintype "power_in"))
      (node (ref "D54") (pin "3") (pinfunction "B+_3") (pintype "power_in"))
      (node (ref "D55") (pin "1") (pinfunction "R+_1") (pintype "power_in"))
      (node (ref "D55") (pin "2") (pinfunction "G+_2") (pintype "power_in"))
      (node (ref "D55") (pin "3") (pinfunction "B+_3") (pintype "power_in"))
      (node (ref "D56") (pin "1") (pinfunction "R+_1") (pintype "power_in"))
      (node (ref "D56") (pin "2") (pinfunction "G+_2") (pintype "power_in"))
      (node (ref "D56") (pin "3") (pinfunction "B+_3") (pintype "power_in"))
      (node (ref "Q7") (pin "4") (pinfunction "P_DRAIN_4") (pintype "passive"))
    )
    (net (code "37") (name "Net-(D57-B+)") (class "Default")
      (node (ref "D57") (pin "1") (pinfunction "R+_1") (pintype "power_in"))
      (node (ref "D57") (pin "2") (pinfunction "G+_2") (pintype "power_in"))
      (node (ref "D57") (pin "3") (pinfunction "B+_3") (pintype "power_in"))
      (node (ref "D58") (pin "1") (pinfunction "R+_1") (pintype "power_in"))
      (node (ref "D58") (pin "2") (pinfunction "G+_2") (pintype "power_in"))
      (node (ref "D58") (pin "3") (pinfunction "B+_3") (pintype "power_in"))
      (node (ref "D59") (pin "1") (pinfunction "R+_1") (pintype "power_in"))
      (node (ref "D59") (pin "2") (pinfunction "G+_2") (pintype "power_in"))
      (node (ref "D59") (pin "3") (pinfunction "B+_3") (pintype "power_in"))
      (node (ref "D60") (pin "1") (pinfunction "R+_1") (pintype "power_in"))
      (node (ref "D60") (pin "2") (pinfunction "G+_2") (pintype "power_in"))
      (node (ref "D60") (pin "3") (pinfunction "B+_3") (pintype "power_in"))
      (node (ref "D61") (pin "1") (pinfunction "R+_1") (pintype "power_in"))
      (node (ref "D61") (pin "2") (pinfunction "G+_2") (pintype "power_in"))
      (node (ref "D61") (pin "3") (pinfunction "B+_3") (pintype "power_in"))
      (node (ref "D62") (pin "1") (pinfunction "R+_1") (pintype "power_in"))
      (node (ref "D62") (pin "2") (pinfunction "G+_2") (pintype "power_in"))
      (node (ref "D62") (pin "3") (pinfunction "B+_3") (pintype "power_in"))
      (node (ref "D63") (pin "1") (pinfunction "R+_1") (pintype "power_in"))
      (node (ref "D63") (pin "2") (pinfunction "G+_2") (pintype "power_in"))
      (node (ref "D63") (pin "3") (pinfunction "B+_3") (pintype "power_in"))
      (node (ref "D64") (pin "1") (pinfunction "R+_1") (pintype "power_in"))
      (node (ref "D64") (pin "2") (pinfunction "G+_2") (pintype "power_in"))
      (node (ref "D64") (pin "3") (pinfunction "B+_3") (pintype "power_in"))
      (node (ref "Q8") (pin "4") (pinfunction "P_DRAIN_4") (pintype "passive"))
    )
    (net (code "38") (name "Net-(Q1-N_DRAIN)") (class "Default")
      (node (ref "Q1") (pin "3") (pinfunction "P_GATE_3") (pintype "passive"))
      (node (ref "Q1") (pin "6") (pinfunction "N_DRAIN_6") (pintype "passive"))
      (node (ref "R1") (pin "1") (pinfunction "1_1") (pintype "passive"))
    )
    (net (code "39") (name "Net-(Q2-N_DRAIN)") (class "Default")
      (node (ref "Q2") (pin "3") (pinfunction "P_GATE_3") (pintype "passive"))
      (node (ref "Q2") (pin "6") (pinfunction "N_DRAIN_6") (pintype "passive"))
      (node (ref "R2") (pin "1") (pinfunction "1_1") (pintype "passive"))
    )
    (net (code "40") (name "Net-(Q3-N_DRAIN)") (class "Default")
      (node (ref "Q3") (pin "3") (pinfunction "P_GATE_3") (pintype "passive"))
      (node (ref "Q3") (pin "6") (pinfunction "N_DRAIN_6") (pintype "passive"))
      (node (ref "R3") (pin "1") (pinfunction "1_1") (pintype "passive"))
    )
    (net (code "41") (name "Net-(Q4-N_DRAIN)") (class "Default")
      (node (ref "Q4") (pin "3") (pinfunction "P_GATE_3") (pintype "passive"))
      (node (ref "Q4") (pin "6") (pinfunction "N_DRAIN_6") (pintype "passive"))
      (node (ref "R4") (pin "1") (pinfunction "1_1") (pintype "passive"))
    )
    (net (code "42") (name "Net-(Q5-N_DRAIN)") (class "Default")
      (node (ref "Q5") (pin "3") (pinfunction "P_GATE_3") (pintype "passive"))
      (node (ref "Q5") (pin "6") (pinfunction "N_DRAIN_6") (pintype "passive"))
      (node (ref "R5") (pin "1") (pinfunction "1_1") (pintype "passive"))
    )
    (net (code "43") (name "Net-(Q6-N_DRAIN)") (class "Default")
      (node (ref "Q6") (pin "3") (pinfunction "P_GATE_3") (pintype "passive"))
      (node (ref "Q6") (pin "6") (pinfunction "N_DRAIN_6") (pintype "passive"))
      (node (ref "R6") (pin "1") (pinfunction "1_1") (pintype "passive"))
    )
    (net (code "44") (name "Net-(Q7-N_DRAIN)") (class "Default")
      (node (ref "Q7") (pin "3") (pinfunction "P_GATE_3") (pintype "passive"))
      (node (ref "Q7") (pin "6") (pinfunction "N_DRAIN_6") (pintype "passive"))
      (node (ref "R7") (pin "1") (pinfunction "1_1") (pintype "passive"))
    )
    (net (code "45") (name "Net-(Q8-N_DRAIN)") (class "Default")
      (node (ref "Q8") (pin "3") (pinfunction "P_GATE_3") (pintype "passive"))
      (node (ref "Q8") (pin "6") (pinfunction "N_DRAIN_6") (pintype "passive"))
      (node (ref "R8") (pin "1") (pinfunction "1_1") (pintype "passive"))
    )
    (net (code "46") (name "VCC") (class "Default")
      (node (ref "Q1") (pin "2") (pinfunction "P_SOURCE_2") (pintype "passive"))
      (node (ref "Q2") (pin "2") (pinfunction "P_SOURCE_2") (pintype "passive"))
      (node (ref "Q3") (pin "2") (pinfunction "P_SOURCE_2") (pintype "passive"))
      (node (ref "Q4") (pin "2") (pinfunction "P_SOURCE_2") (pintype "passive"))
      (node (ref "Q5") (pin "2") (pinfunction "P_SOURCE_2") (pintype "passive"))
      (node (ref "Q6") (pin "2") (pinfunction "P_SOURCE_2") (pintype "passive"))
      (node (ref "Q7") (pin "2") (pinfunction "P_SOURCE_2") (pintype "passive"))
      (node (ref "Q8") (pin "2") (pinfunction "P_SOURCE_2") (pintype "passive"))
      (node (ref "R1") (pin "2") (pinfunction "2_2") (pintype "passive"))
      (node (ref "R2") (pin "2") (pinfunction "2_2") (pintype "passive"))
      (node (ref "R3") (pin "2") (pinfunction "2_2") (pintype "passive"))
      (node (ref "R4") (pin "2") (pinfunction "2_2") (pintype "passive"))
      (node (ref "R5") (pin "2") (pinfunction "2_2") (pintype "passive"))
      (node (ref "R6") (pin "2") (pinfunction "2_2") (pintype "passive"))
      (node (ref "R7") (pin "2") (pinfunction "2_2") (pintype "passive"))
      (node (ref "R8") (pin "2") (pinfunction "2_2") (pintype "passive"))
    )
    (net (code "47") (name "unconnected-(Q1-N_GATE-Pad1)") (class "Default")
      (node (ref "Q1") (pin "1") (pinfunction "N_GATE_1") (pintype "passive"))
    )
    (net (code "48") (name "unconnected-(Q2-N_GATE-Pad1)") (class "Default")
      (node (ref "Q2") (pin "1") (pinfunction "N_GATE_1") (pintype "passive"))
    )
    (net (code "49") (name "unconnected-(Q3-N_GATE-Pad1)") (class "Default")
      (node (ref "Q3") (pin "1") (pinfunction "N_GATE_1") (pintype "passive"))
    )
    (net (code "50") (name "unconnected-(Q4-N_GATE-Pad1)") (class "Default")
      (node (ref "Q4") (pin "1") (pinfunction "N_GATE_1") (pintype "passive"))
    )
    (net (code "51") (name "unconnected-(Q5-N_GATE-Pad1)") (class "Default")
      (node (ref "Q5") (pin "1") (pinfunction "N_GATE_1") (pintype "passive"))
    )
    (net (code "52") (name "unconnected-(Q6-N_GATE-Pad1)") (class "Default")
      (node (ref "Q6") (pin "1") (pinfunction "N_GATE_1") (pintype "passive"))
    )
    (net (code "53") (name "unconnected-(Q7-N_GATE-Pad1)") (class "Default")
      (node (ref "Q7") (pin "1") (pinfunction "N_GATE_1") (pintype "passive"))
    )
    (net (code "54") (name "unconnected-(Q8-N_GATE-Pad1)") (class "Default")
      (node (ref "Q8") (pin "1") (pinfunction "N_GATE_1") (pintype "passive"))
    )
  )
)
